# 12_Clock_2.net
KiCad netlist of a schematic drawn in Altium Designer
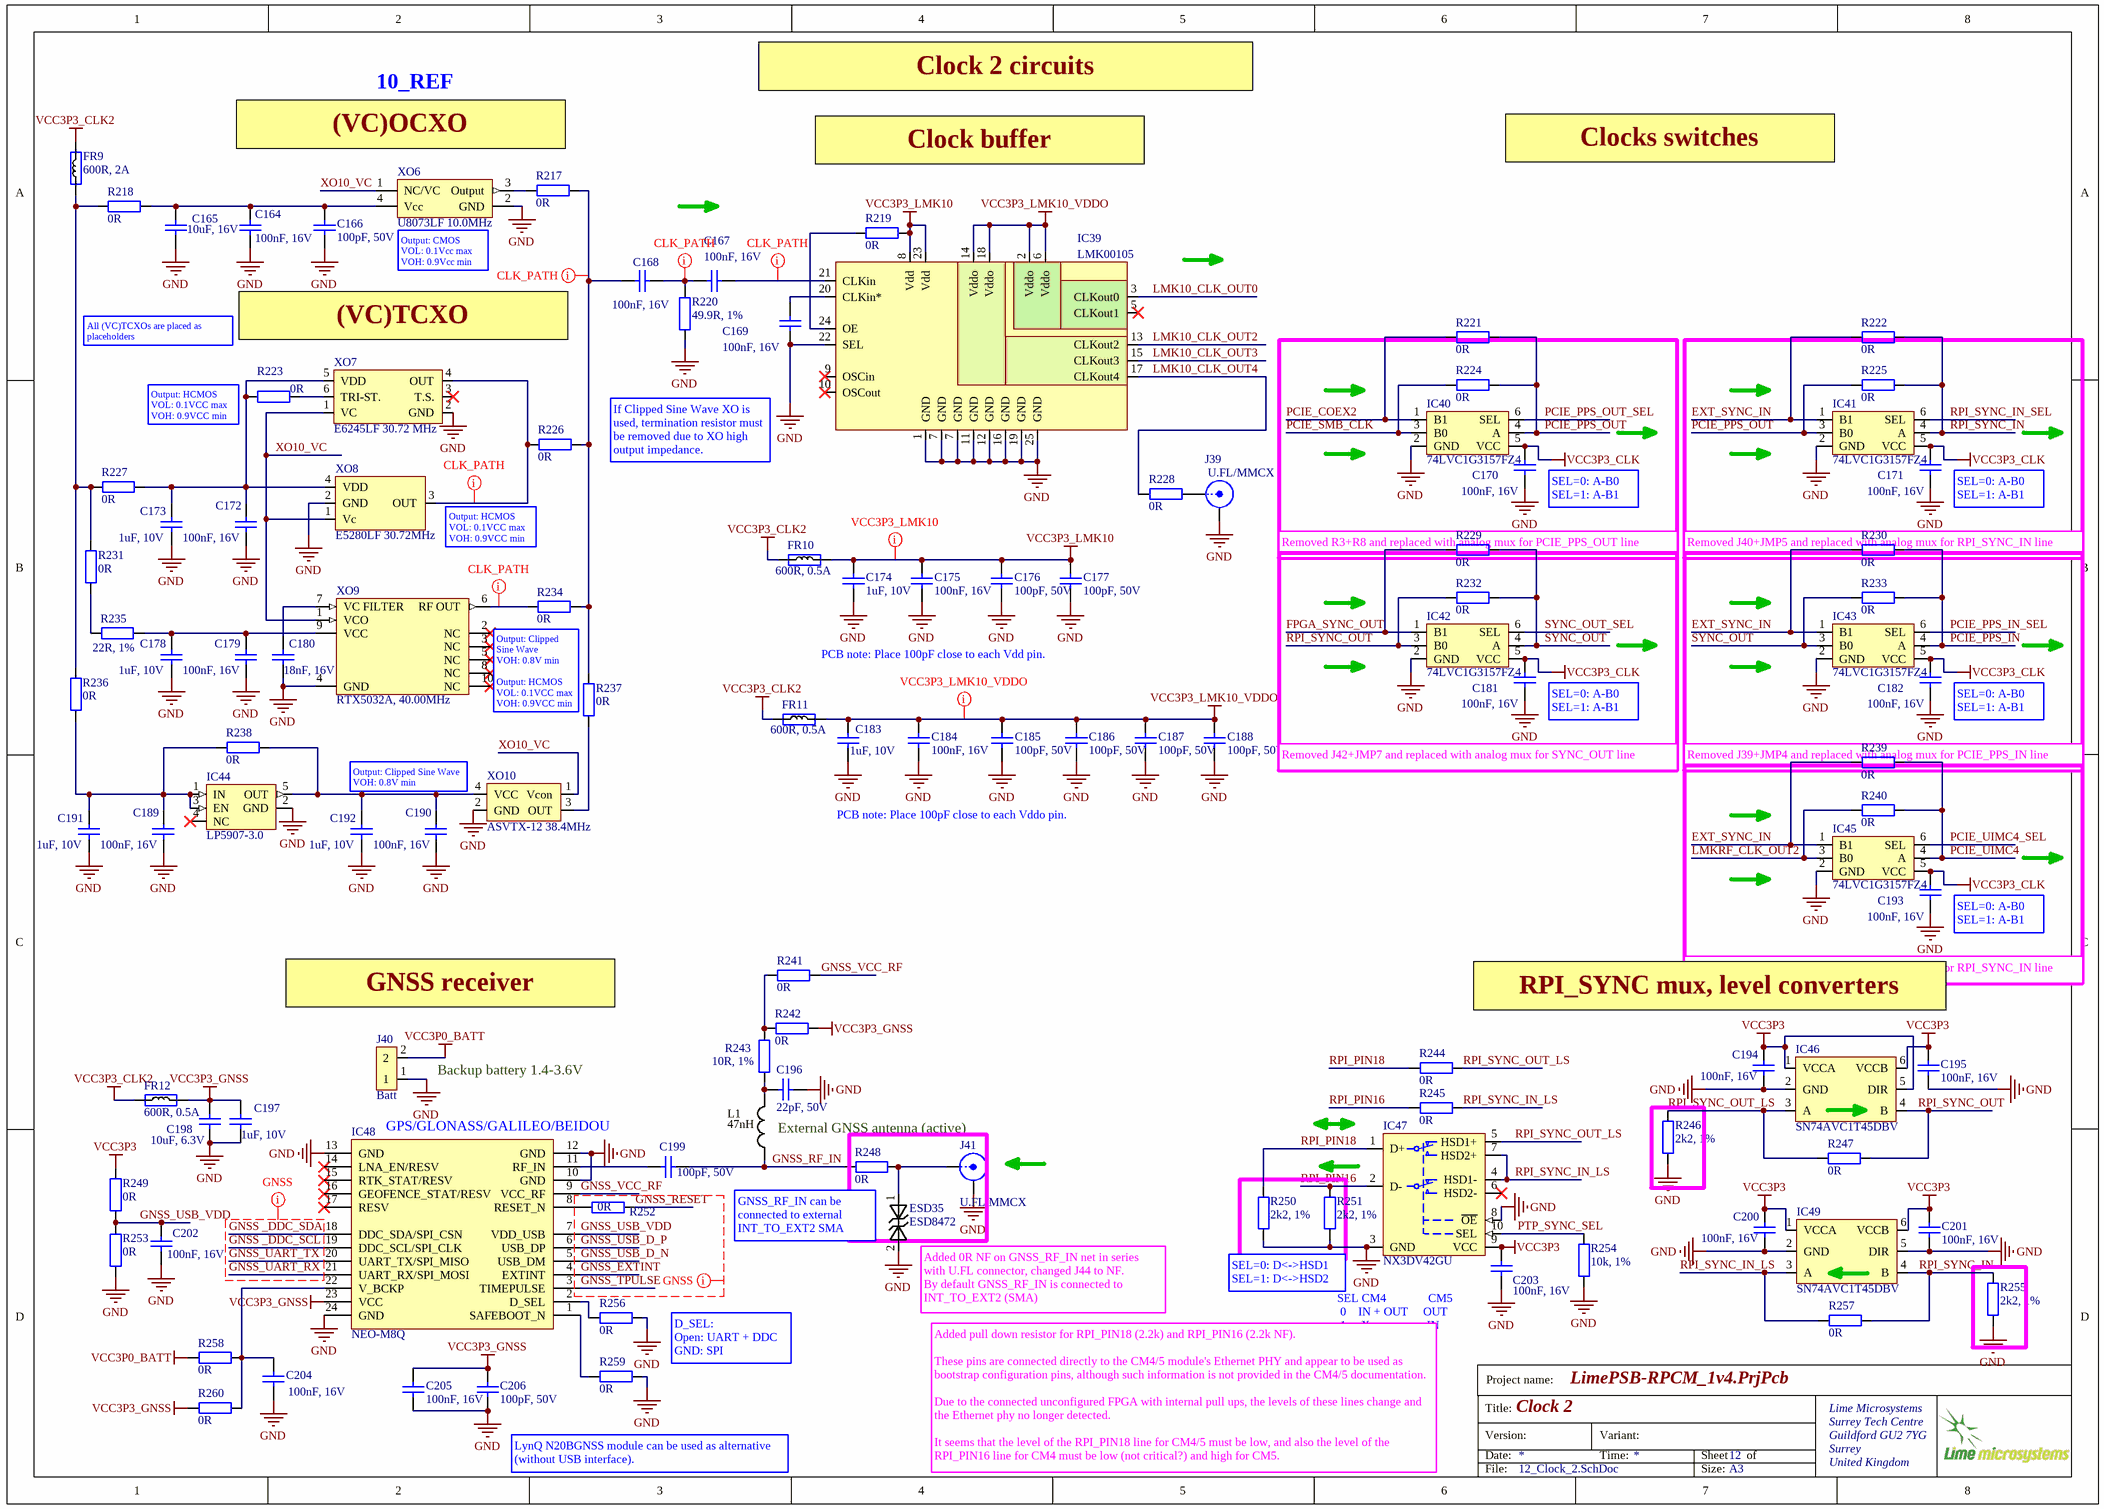
[diagram p0: 12_Clock_2.SchDoc]

(export (version "E")
  (design (tool "Eeschema 10.0.6"))
  (components
    (comp (ref "C164")
      (value "100nF, 16V")
      (footprint "CAP0402")
      (fields
        (field (name "MANUFACTURER") "Murata Electronics")
        (field (name "TOLERANCE") "10 %")
        (field (name "MANUFACTURER PART NUMBER") "GRM155R71C104KA88D")
      )
      (libsource (lib "LimeMicroAltiumLib_schLib") (part "Cap_0402"))
    )
    (comp (ref "C165")
      (value "10uF, 16V")
      (footprint "CAP0603")
      (fields (field (name "MANUFACTURER") "Yageo") (field (name "TOLERANCE") "±20%"))
      (libsource (lib "LimeMicroAltiumLib_schLib") (part "Cap_0603"))
    )
    (comp (ref "C166")
      (value "100pF, 50V")
      (footprint "CAP0402")
      (fields (field (name "TOLERANCE") "±5%") (field (name "MANUFACTURER") "Yageo"))
      (libsource (lib "LimeMicroAltiumLib_schLib") (part "Cap_0402"))
    )
    (comp (ref "C167")
      (value "100nF, 16V")
      (footprint "CAP0402")
      (fields
        (field (name "MANUFACTURER") "Murata Electronics")
        (field (name "TOLERANCE") "10 %")
        (field (name "MANUFACTURER PART NUMBER") "GRM155R71C104KA88D")
      )
      (libsource (lib "LimeMicroAltiumLib_schLib") (part "Cap_0402"))
    )
    (comp (ref "C168")
      (value "100nF, 16V")
      (footprint "CAP0402")
      (fields
        (field (name "MANUFACTURER") "Murata Electronics")
        (field (name "TOLERANCE") "10 %")
        (field (name "MANUFACTURER PART NUMBER") "GRM155R71C104KA88D")
      )
      (libsource (lib "LimeMicroAltiumLib_schLib") (part "Cap_0402"))
    )
    (comp (ref "C169")
      (value "100nF, 16V")
      (footprint "CAP0402")
      (fields
        (field (name "MANUFACTURER") "Murata Electronics")
        (field (name "TOLERANCE") "10 %")
        (field (name "MANUFACTURER PART NUMBER") "GRM155R71C104KA88D")
      )
      (libsource (lib "LimeMicroAltiumLib_schLib") (part "Cap_0402"))
    )
    (comp (ref "C170")
      (value "100nF, 16V")
      (footprint "CAP0402")
      (fields
        (field (name "MANUFACTURER") "Murata Electronics")
        (field (name "TOLERANCE") "10 %")
        (field (name "MANUFACTURER PART NUMBER") "GRM155R71C104KA88D")
      )
      (libsource (lib "LimeMicroAltiumLib_schLib") (part "Cap_0402"))
    )
    (comp (ref "C171")
      (value "100nF, 16V")
      (footprint "CAP0402")
      (fields
        (field (name "MANUFACTURER") "Murata Electronics")
        (field (name "TOLERANCE") "10 %")
        (field (name "MANUFACTURER PART NUMBER") "GRM155R71C104KA88D")
      )
      (libsource (lib "LimeMicroAltiumLib_schLib") (part "Cap_0402"))
    )
    (comp (ref "C172")
      (value "100nF, 16V")
      (footprint "CAP0402")
      (fields
        (field (name "MANUFACTURER") "Murata Electronics")
        (field (name "TOLERANCE") "10 %")
        (field (name "MANUFACTURER PART NUMBER") "GRM155R71C104KA88D")
      )
      (libsource (lib "LimeMicroAltiumLib_schLib") (part "Cap_0402"))
    )
    (comp (ref "C173")
      (value "1uF, 10V")
      (footprint "CAP0402")
      (description "CAP CER 1UF 10V X5R 0402")
      (fields (field (name "MANUFACTURER") "Yageo"))
      (libsource (lib "LimeMicroAltiumLib_schLib") (part "Cap_0402"))
    )
    (comp (ref "C174")
      (value "1uF, 10V")
      (footprint "CAP0402")
      (description "CAP CER 1UF 10V X5R 0402")
      (fields (field (name "MANUFACTURER") "Yageo") (field (name "TOLERANCE") "±20%"))
      (libsource (lib "LimeMicroAltiumLib_schLib") (part "Cap_0402"))
    )
    (comp (ref "C175")
      (value "100nF, 16V")
      (footprint "CAP0402")
      (fields
        (field (name "MANUFACTURER") "Murata Electronics")
        (field (name "TOLERANCE") "10 %")
        (field (name "MANUFACTURER PART NUMBER") "GRM155R71C104KA88D")
      )
      (libsource (lib "LimeMicroAltiumLib_schLib") (part "Cap_0402"))
    )
    (comp (ref "C176")
      (value "100pF, 50V")
      (footprint "CAP0402")
      (fields (field (name "MANUFACTURER") "Yageo") (field (name "TOLERANCE") "±5%"))
      (libsource (lib "LimeMicroAltiumLib_schLib") (part "Cap_0402"))
    )
    (comp (ref "C177")
      (value "100pF, 50V")
      (footprint "CAP0402")
      (fields (field (name "MANUFACTURER") "Yageo") (field (name "TOLERANCE") "±5%"))
      (libsource (lib "LimeMicroAltiumLib_schLib") (part "Cap_0402"))
    )
    (comp (ref "C178")
      (value "1uF, 10V")
      (footprint "CAP0402")
      (description "CAP CER 1UF 10V X5R 0402")
      (fields (field (name "MANUFACTURER") "Yageo"))
      (libsource (lib "LimeMicroAltiumLib_schLib") (part "Cap_0402"))
    )
    (comp (ref "C179")
      (value "100nF, 16V")
      (footprint "CAP0402")
      (fields
        (field (name "MANUFACTURER") "Murata Electronics")
        (field (name "TOLERANCE") "10 %")
        (field (name "MANUFACTURER PART NUMBER") "GRM155R71C104KA88D")
      )
      (libsource (lib "LimeMicroAltiumLib_schLib") (part "Cap_0402"))
    )
    (comp (ref "C180")
      (value "18nF, 16V")
      (footprint "CAP0402")
      (fields (field (name "MANUFACTURER") "Yageo") (field (name "TOLERANCE") "±10%"))
      (libsource (lib "LimeMicroAltiumLib_schLib") (part "Cap_0402"))
    )
    (comp (ref "C181")
      (value "100nF, 16V")
      (footprint "CAP0402")
      (fields
        (field (name "MANUFACTURER") "Murata Electronics")
        (field (name "TOLERANCE") "10 %")
        (field (name "MANUFACTURER PART NUMBER") "GRM155R71C104KA88D")
      )
      (libsource (lib "LimeMicroAltiumLib_schLib") (part "Cap_0402"))
    )
    (comp (ref "C182")
      (value "100nF, 16V")
      (footprint "CAP0402")
      (fields
        (field (name "MANUFACTURER") "Murata Electronics")
        (field (name "TOLERANCE") "10 %")
        (field (name "MANUFACTURER PART NUMBER") "GRM155R71C104KA88D")
      )
      (libsource (lib "LimeMicroAltiumLib_schLib") (part "Cap_0402"))
    )
    (comp (ref "C183")
      (value "1uF, 10V")
      (footprint "CAP0402")
      (description "CAP CER 1UF 10V X5R 0402")
      (fields (field (name "MANUFACTURER") "Yageo") (field (name "TOLERANCE") "±20%"))
      (libsource (lib "LimeMicroAltiumLib_schLib") (part "Cap_0402"))
    )
    (comp (ref "C184")
      (value "100nF, 16V")
      (footprint "CAP0402")
      (fields
        (field (name "MANUFACTURER") "Murata Electronics")
        (field (name "TOLERANCE") "10 %")
        (field (name "MANUFACTURER PART NUMBER") "GRM155R71C104KA88D")
      )
      (libsource (lib "LimeMicroAltiumLib_schLib") (part "Cap_0402"))
    )
    (comp (ref "C185")
      (value "100pF, 50V")
      (footprint "CAP0402")
      (fields (field (name "MANUFACTURER") "Yageo") (field (name "TOLERANCE") "±5%"))
      (libsource (lib "LimeMicroAltiumLib_schLib") (part "Cap_0402"))
    )
    (comp (ref "C186")
      (value "100pF, 50V")
      (footprint "CAP0402")
      (fields (field (name "MANUFACTURER") "Yageo") (field (name "TOLERANCE") "±5%"))
      (libsource (lib "LimeMicroAltiumLib_schLib") (part "Cap_0402"))
    )
    (comp (ref "C187")
      (value "100pF, 50V")
      (footprint "CAP0402")
      (fields (field (name "MANUFACTURER") "Yageo") (field (name "TOLERANCE") "±5%"))
      (libsource (lib "LimeMicroAltiumLib_schLib") (part "Cap_0402"))
    )
    (comp (ref "C188")
      (value "100pF, 50V")
      (footprint "CAP0402")
      (fields (field (name "MANUFACTURER") "Yageo") (field (name "TOLERANCE") "±5%"))
      (libsource (lib "LimeMicroAltiumLib_schLib") (part "Cap_0402"))
    )
    (comp (ref "C189")
      (value "100nF, 16V")
      (footprint "CAP0402")
      (fields
        (field (name "MANUFACTURER") "Murata Electronics")
        (field (name "TOLERANCE") "10 %")
        (field (name "MANUFACTURER PART NUMBER") "GRM155R71C104KA88D")
      )
      (libsource (lib "") (part "Cap_0402_1"))
    )
    (comp (ref "C190")
      (value "100nF, 16V")
      (footprint "CAP0402")
      (fields
        (field (name "MANUFACTURER") "Murata Electronics")
        (field (name "TOLERANCE") "10 %")
        (field (name "MANUFACTURER PART NUMBER") "GRM155R71C104KA88D")
      )
      (libsource (lib "") (part "Cap_0402_1"))
    )
    (comp (ref "C191")
      (value "1uF, 10V")
      (footprint "CAP0402")
      (fields (field (name "MANUFACTURER") "Yageo"))
      (libsource (lib "") (part "Cap_0402_1"))
    )
    (comp (ref "C192")
      (value "1uF, 10V")
      (footprint "CAP0402")
      (fields (field (name "MANUFACTURER") "Yageo"))
      (libsource (lib "") (part "Cap_0402_1"))
    )
    (comp (ref "C193")
      (value "100nF, 16V")
      (footprint "CAP0402")
      (fields
        (field (name "MANUFACTURER") "Murata Electronics")
        (field (name "TOLERANCE") "10 %")
        (field (name "MANUFACTURER PART NUMBER") "GRM155R71C104KA88D")
      )
      (libsource (lib "LimeMicroAltiumLib_schLib") (part "Cap_0402"))
    )
    (comp (ref "C194")
      (value "100nF, 16V")
      (footprint "CAP0402")
      (fields
        (field (name "MANUFACTURER") "Murata Electronics")
        (field (name "TOLERANCE") "10 %")
        (field (name "MANUFACTURER PART NUMBER") "GRM155R71C104KA88D")
      )
      (libsource (lib "LimeMicroAltiumLib_schLib") (part "Cap_0402"))
    )
    (comp (ref "C195")
      (value "100nF, 16V")
      (footprint "CAP0402")
      (fields
        (field (name "MANUFACTURER") "Murata Electronics")
        (field (name "TOLERANCE") "10 %")
        (field (name "MANUFACTURER PART NUMBER") "GRM155R71C104KA88D")
      )
      (libsource (lib "LimeMicroAltiumLib_schLib") (part "Cap_0402"))
    )
    (comp (ref "C196")
      (value "22pF, 50V")
      (footprint "CAP0402")
      (fields (field (name "TOLERANCE") "±5%") (field (name "MANUFACTURER") "Yageo"))
      (libsource (lib "LimeMicroAltiumLib_schLib") (part "Cap_0402"))
    )
    (comp (ref "C197")
      (value "1uF, 10V")
      (footprint "CAP0402")
      (description "CAP CER 1UF 10V X5R 0402")
      (fields (field (name "MANUFACTURER") "Yageo") (field (name "TOLERANCE") "±20%"))
      (libsource (lib "LimeMicroAltiumLib_schLib") (part "Cap_0402"))
    )
    (comp (ref "C198")
      (value "10uF, 6.3V")
      (footprint "CAP0603")
      (fields (field (name "TOLERANCE") "±20%") (field (name "MANUFACTURER") "Yageo"))
      (libsource (lib "LimeFPGAboard_schLib") (part "Cap_0603"))
    )
    (comp (ref "C199")
      (value "100pF, 50V")
      (footprint "CAP0402")
      (fields (field (name "TOLERANCE") "±5%") (field (name "MANUFACTURER") "Yageo"))
      (libsource (lib "LimeMicroAltiumLib_schLib") (part "Cap_0402"))
    )
    (comp (ref "C200")
      (value "100nF, 16V")
      (footprint "CAP0402")
      (fields
        (field (name "MANUFACTURER") "Murata Electronics")
        (field (name "TOLERANCE") "10 %")
        (field (name "MANUFACTURER PART NUMBER") "GRM155R71C104KA88D")
      )
      (libsource (lib "LimeMicroAltiumLib_schLib") (part "Cap_0402"))
    )
    (comp (ref "C201")
      (value "100nF, 16V")
      (footprint "CAP0402")
      (fields
        (field (name "MANUFACTURER") "Murata Electronics")
        (field (name "TOLERANCE") "10 %")
        (field (name "MANUFACTURER PART NUMBER") "GRM155R71C104KA88D")
      )
      (libsource (lib "LimeMicroAltiumLib_schLib") (part "Cap_0402"))
    )
    (comp (ref "C202")
      (value "100nF, 16V")
      (footprint "CAP0402")
      (fields
        (field (name "TOLERANCE") "10 %")
        (field (name "MANUFACTURER") "Murata Electronics")
        (field (name "MANUFACTURER PART NUMBER") "GRM155R71C104KA88D")
      )
      (libsource (lib "LimeFPGAboard_schLib") (part "Cap_0603"))
    )
    (comp (ref "C203")
      (value "100nF, 16V")
      (footprint "CAP0402")
      (fields
        (field (name "MANUFACTURER") "Murata Electronics")
        (field (name "TOLERANCE") "10 %")
        (field (name "MANUFACTURER PART NUMBER") "GRM155R71C104KA88D")
      )
      (libsource (lib "LimeMicroAltiumLib_schLib") (part "Cap_0402"))
    )
    (comp (ref "C204")
      (value "100nF, 16V")
      (footprint "CAP0402")
      (fields
        (field (name "TOLERANCE") "10 %")
        (field (name "MANUFACTURER") "Murata Electronics")
        (field (name "MANUFACTURER PART NUMBER") "GRM155R71C104KA88D")
      )
      (libsource (lib "LimeFPGAboard_schLib") (part "Cap_0603"))
    )
    (comp (ref "C205")
      (value "100nF, 16V")
      (footprint "CAP0402")
      (fields
        (field (name "MANUFACTURER") "Murata Electronics")
        (field (name "TOLERANCE") "10 %")
        (field (name "MANUFACTURER PART NUMBER") "GRM155R71C104KA88D")
      )
      (libsource (lib "LimeMicroAltiumLib_schLib") (part "Cap_0402"))
    )
    (comp (ref "C206")
      (value "100pF, 50V")
      (footprint "CAP0402")
      (fields (field (name "TOLERANCE") "±5%") (field (name "MANUFACTURER") "Yageo"))
      (libsource (lib "LimeMicroAltiumLib_schLib") (part "Cap_0402"))
    )
    (comp (ref "ESD35")
      (value "ESD8472")
      (footprint "ESD8472_X3DFN2")
      (fields
        (field (name "MANUFACTURER") "ON Semiconductor")
        (field (name "MANUFACTURER PART NUMBER") "ESD8472MUT5G")
      )
      (libsource (lib "LimeMicroAltiumLib_schLib") (part "ESD8472"))
    )
    (comp (ref "FR9")
      (value "600R, 2A")
      (footprint "RES0805")
      (fields (field (name "MANUFACTURER") "TDK Corporation"))
      (libsource (lib "LimeFPGAboard_schLib") (part "Ferrite"))
    )
    (comp (ref "FR10")
      (value "600R, 0.5A")
      (footprint "RES0402")
      (fields (field (name "MANUFACTURER") "Murata") (field (name "TOLERANCE") "25%"))
      (libsource (lib "LimeMicroAltiumLib_schLib") (part "Ferrite"))
    )
    (comp (ref "FR11")
      (value "600R, 0.5A")
      (footprint "RES0402")
      (fields (field (name "MANUFACTURER") "Murata") (field (name "TOLERANCE") "25%"))
      (libsource (lib "LimeMicroAltiumLib_schLib") (part "Ferrite"))
    )
    (comp (ref "FR12")
      (value "600R, 0.5A")
      (footprint "RES0402")
      (fields (field (name "MANUFACTURER") "Murata") (field (name "TOLERANCE") "25%"))
      (libsource (lib "LimeMicroAltiumLib_schLib") (part "Ferrite"))
    )
    (comp (ref "IC39")
      (value "LMK00105")
      (footprint "LMK00105SQ")
      (fields (field (name "MANUFACTURER") "Texas Instruments"))
      (libsource (lib "LimeMicroAltiumLib_schLib") (part "LMK00105"))
    )
    (comp (ref "IC40")
      (value "74LVC1G3157FZ4")
      (footprint "74LVC1G3157FZ4_SPDT_SW_DFN1410-6")
      (fields (field (name "MANUFACTURER") "Diodes"))
      (libsource (lib "LimeMicroAltiumLib_schLib_r04") (part "74LVC1G3157FZ4_SPDT_SW"))
    )
    (comp (ref "IC41")
      (value "74LVC1G3157FZ4")
      (footprint "74LVC1G3157FZ4_SPDT_SW_DFN1410-6")
      (fields (field (name "MANUFACTURER") "Diodes"))
      (libsource (lib "LimeMicroAltiumLib_schLib_r04") (part "74LVC1G3157FZ4_SPDT_SW"))
    )
    (comp (ref "IC42")
      (value "74LVC1G3157FZ4")
      (footprint "74LVC1G3157FZ4_SPDT_SW_DFN1410-6")
      (fields (field (name "MANUFACTURER") "Diodes"))
      (libsource (lib "LimeMicroAltiumLib_schLib_r04") (part "74LVC1G3157FZ4_SPDT_SW"))
    )
    (comp (ref "IC43")
      (value "74LVC1G3157FZ4")
      (footprint "74LVC1G3157FZ4_SPDT_SW_DFN1410-6")
      (fields (field (name "MANUFACTURER") "Diodes"))
      (libsource (lib "LimeMicroAltiumLib_schLib_r04") (part "74LVC1G3157FZ4_SPDT_SW"))
    )
    (comp (ref "IC44")
      (value "LP5907-3.0")
      (footprint "SOT23-5")
      (fields (field (name "MANUFACTURER") "Texas Instruments"))
      (libsource (lib "LimeMicroAltiumLib_schLib_r01") (part "LP5907"))
    )
    (comp (ref "IC45")
      (value "74LVC1G3157FZ4")
      (footprint "74LVC1G3157FZ4_SPDT_SW_DFN1410-6")
      (fields (field (name "MANUFACTURER") "Diodes"))
      (libsource (lib "LimeMicroAltiumLib_schLib_r04") (part "74LVC1G3157FZ4_SPDT_SW"))
    )
    (comp (ref "IC46")
      (value "SN74AVC1T45DBV")
      (footprint "SOT23-6")
      (fields (field (name "MANUFACTURER") "Texas Instruments"))
      (libsource (lib "LimeMicroAltiumLib_schLib_r04") (part "SN74AVC1T45DBV"))
    )
    (comp (ref "IC47")
      (value "NX3DV42GU")
      (footprint "FSUSB42UMX")
      (fields (field (name "MANUFACTURER") "NXP Semiconductors"))
      (libsource (lib "LimeMicroAltiumLib_schLib_r01") (part "FSUSB42UMX"))
    )
    (comp (ref "IC48")
      (value "NEO-M8Q")
      (footprint "NEO-7M/8M")
      (description "GNSS engine for GPS/QZSS, GLONASS")
      (fields (field (name "MANUFACTURER") "U-blox"))
      (libsource (lib "LimeMicroAltiumLib_schLib") (part "NEO-M8P_M8M"))
    )
    (comp (ref "IC49")
      (value "SN74AVC1T45DBV")
      (footprint "SOT23-6")
      (fields (field (name "MANUFACTURER") "Texas Instruments"))
      (libsource (lib "LimeMicroAltiumLib_schLib_r04") (part "SN74AVC1T45DBV"))
    )
    (comp (ref "J39")
      (value "U.FL/MMCX")
      (footprint "MMCX_UFL_conn_u")
      (description "CONN UMC RCPT STR 50 OHM SMD")
      (fields (field (name "MANUFACTURER") "Molex, LLC"))
      (libsource (lib "LimeMicroAltiumLib_schLib") (part "RF_IF_connector"))
    )
    (comp (ref "J40")
      (value "Batt")
      (footprint "HDR_1x2")
      (fields (field (name "MANUFACTURER") "3M"))
      (libsource (lib "LimeFPGAboard_schLib") (part "Jumper"))
    )
    (comp (ref "J41")
      (value "U.FL/MMCX")
      (footprint "MMCX_UFL_conn_u")
      (description "CONN UMC RCPT STR 50 OHM SMD")
      (fields (field (name "MANUFACTURER") "Molex, LLC"))
      (libsource (lib "LimeMicroAltiumLib_schLib") (part "RF_IF_connector"))
    )
    (comp (ref "L1")
      (value "47nH")
      (footprint "RES0402")
      (fields
        (field (name "MANUFACTURER") "COILCRAFT")
        (field (name "MANUFACTURER PART NUMBER") "0402HP-47NXJLU")
      )
      (libsource (lib "LimeMicroAltiumLib_schLib") (part "Inductor_0603"))
    )
    (comp (ref "R217")
      (value "0R")
      (footprint "RES0402_v2")
      (fields (field (name "MANUFACTURER") "Yageo") (field (name "TOLERANCE") "Jumper"))
      (libsource (lib "LimeMicroAltiumLib_schLib") (part "Res_0402"))
    )
    (comp (ref "R218")
      (value "0R")
      (footprint "RES0402")
      (fields (field (name "MANUFACTURER") "Yageo") (field (name "TOLERANCE") "Jumper"))
      (libsource (lib "LimeMicroAltiumLib_schLib") (part "Res_0402"))
    )
    (comp (ref "R219")
      (value "0R")
      (footprint "RES0402")
      (fields (field (name "MANUFACTURER") "Yageo") (field (name "TOLERANCE") "Jumper"))
      (libsource (lib "LimeMicroAltiumLib_schLib") (part "Res_0402"))
    )
    (comp (ref "R220")
      (value "49.9R, 1%")
      (footprint "RES0402")
      (fields
        (field (name "TOLERANCE") "±1%")
        (field (name "MANUFACTURER") "Samsung Electro-Mechanics America, Inc.")
      )
      (libsource (lib "LimeMicroAltiumLib_schLib") (part "Res_0402"))
    )
    (comp (ref "R221")
      (value "0R")
      (footprint "RES0402_v2")
      (fields (field (name "MANUFACTURER") "Yageo") (field (name "TOLERANCE") "Jumper"))
      (libsource (lib "LimeMicroAltiumLib_schLib") (part "Res_0402"))
    )
    (comp (ref "R222")
      (value "0R")
      (footprint "RES0402_v2")
      (fields (field (name "MANUFACTURER") "Yageo") (field (name "TOLERANCE") "Jumper"))
      (libsource (lib "LimeMicroAltiumLib_schLib") (part "Res_0402"))
    )
    (comp (ref "R223")
      (value "0R")
      (footprint "RES0402")
      (fields (field (name "MANUFACTURER") "Yageo") (field (name "TOLERANCE") "Jumper"))
      (libsource (lib "LimeMicroAltiumLib_schLib") (part "Res_0402"))
    )
    (comp (ref "R224")
      (value "0R")
      (footprint "RES0402_v2")
      (fields (field (name "MANUFACTURER") "Yageo") (field (name "TOLERANCE") "Jumper"))
      (libsource (lib "LimeMicroAltiumLib_schLib") (part "Res_0402"))
    )
    (comp (ref "R225")
      (value "0R")
      (footprint "RES0402_v2")
      (fields (field (name "MANUFACTURER") "Yageo") (field (name "TOLERANCE") "Jumper"))
      (libsource (lib "LimeMicroAltiumLib_schLib") (part "Res_0402"))
    )
    (comp (ref "R226")
      (value "0R")
      (footprint "RES0402_v2")
      (fields (field (name "MANUFACTURER") "Yageo") (field (name "TOLERANCE") "Jumper"))
      (libsource (lib "LimeMicroAltiumLib_schLib") (part "Res_0402"))
    )
    (comp (ref "R227")
      (value "0R")
      (footprint "RES0402")
      (fields (field (name "MANUFACTURER") "Yageo") (field (name "TOLERANCE") "Jumper"))
      (libsource (lib "LimeMicroAltiumLib_schLib") (part "Res_0402"))
    )
    (comp (ref "R228")
      (value "0R")
      (footprint "RES0402")
      (fields (field (name "MANUFACTURER") "Yageo") (field (name "TOLERANCE") "Jumper"))
      (libsource (lib "") (part "Res_0402_1"))
    )
    (comp (ref "R229")
      (value "0R")
      (footprint "RES0402_v2")
      (fields (field (name "MANUFACTURER") "Yageo") (field (name "TOLERANCE") "Jumper"))
      (libsource (lib "LimeMicroAltiumLib_schLib") (part "Res_0402"))
    )
    (comp (ref "R230")
      (value "0R")
      (footprint "RES0402_v2")
      (fields (field (name "MANUFACTURER") "Yageo") (field (name "TOLERANCE") "Jumper"))
      (libsource (lib "LimeMicroAltiumLib_schLib") (part "Res_0402"))
    )
    (comp (ref "R231")
      (value "0R")
      (footprint "RES0402")
      (fields (field (name "MANUFACTURER") "Yageo") (field (name "TOLERANCE") "Jumper"))
      (libsource (lib "LimeMicroAltiumLib_schLib") (part "Res_0402"))
    )
    (comp (ref "R232")
      (value "0R")
      (footprint "RES0402_v2")
      (fields (field (name "MANUFACTURER") "Yageo") (field (name "TOLERANCE") "Jumper"))
      (libsource (lib "LimeMicroAltiumLib_schLib") (part "Res_0402"))
    )
    (comp (ref "R233")
      (value "0R")
      (footprint "RES0402_v2")
      (fields (field (name "MANUFACTURER") "Yageo") (field (name "TOLERANCE") "Jumper"))
      (libsource (lib "LimeMicroAltiumLib_schLib") (part "Res_0402"))
    )
    (comp (ref "R234")
      (value "0R")
      (footprint "RES0402_v2")
      (fields (field (name "MANUFACTURER") "Yageo") (field (name "TOLERANCE") "Jumper"))
      (libsource (lib "LimeMicroAltiumLib_schLib") (part "Res_0402"))
    )
    (comp (ref "R235")
      (value "22R, 1%")
      (footprint "RES0402")
      (fields (field (name "TOLERANCE") "±1%") (field (name "MANUFACTURER") "Yageo"))
      (libsource (lib "LimeFPGAboard_schLib") (part "Res_0402"))
    )
    (comp (ref "R236")
      (value "0R")
      (footprint "RES0402")
      (fields (field (name "MANUFACTURER") "Yageo") (field (name "TOLERANCE") "Jumper"))
      (libsource (lib "") (part "Res_0402_1"))
    )
    (comp (ref "R237")
      (value "0R")
      (footprint "RES0402_v2")
      (fields (field (name "MANUFACTURER") "Yageo") (field (name "TOLERANCE") "Jumper"))
      (libsource (lib "") (part "Res_0402_1"))
    )
    (comp (ref "R238")
      (value "0R")
      (footprint "RES0402")
      (fields (field (name "MANUFACTURER") "Yageo") (field (name "TOLERANCE") "Jumper"))
      (libsource (lib "") (part "Res_0402_1"))
    )
    (comp (ref "R239")
      (value "0R")
      (footprint "RES0402_v2")
      (fields (field (name "MANUFACTURER") "Yageo") (field (name "TOLERANCE") "Jumper"))
      (libsource (lib "LimeMicroAltiumLib_schLib") (part "Res_0402"))
    )
    (comp (ref "R240")
      (value "0R")
      (footprint "RES0402_v2")
      (fields (field (name "MANUFACTURER") "Yageo") (field (name "TOLERANCE") "Jumper"))
      (libsource (lib "LimeMicroAltiumLib_schLib") (part "Res_0402"))
    )
    (comp (ref "R241")
      (value "0R")
      (footprint "RES0402")
      (fields (field (name "MANUFACTURER") "Yageo") (field (name "TOLERANCE") "Jumper"))
      (libsource (lib "LimeMicroAltiumLib_schLib") (part "Res_0402"))
    )
    (comp (ref "R242")
      (value "0R")
      (footprint "RES0402")
      (fields (field (name "MANUFACTURER") "Yageo") (field (name "TOLERANCE") "Jumper"))
      (libsource (lib "LimeMicroAltiumLib_schLib") (part "Res_0402"))
    )
    (comp (ref "R243")
      (value "10R, 1%")
      (footprint "RES0402")
      (fields (field (name "MANUFACTURER") "Stackpole Electronics") (field (name "TOLERANCE") "1%"))
      (libsource (lib "LimeMicroAltiumLib_schLib") (part "Res_0402"))
    )
    (comp (ref "R244")
      (value "0R")
      (footprint "RES0402")
      (fields (field (name "MANUFACTURER") "Yageo") (field (name "TOLERANCE") "Jumper"))
      (libsource (lib "") (part "Res_0402_1"))
    )
    (comp (ref "R245")
      (value "0R")
      (footprint "RES0402")
      (fields (field (name "MANUFACTURER") "Yageo") (field (name "TOLERANCE") "Jumper"))
      (libsource (lib "") (part "Res_0402_1"))
    )
    (comp (ref "R246")
      (value "2k2, 1%")
      (footprint "RES0402")
      (fields (field (name "MANUFACTURER") "Stackpole Electronics Inc") (field (name "TOLERANCE") "±1%"))
      (libsource (lib "LimeMicroAltiumLib_schLib") (part "Res_0402"))
    )
    (comp (ref "R247")
      (value "0R")
      (footprint "RES0402")
      (fields (field (name "MANUFACTURER") "Yageo") (field (name "TOLERANCE") "Jumper"))
      (libsource (lib "LimeFPGAboard_schLib") (part "Res_0402"))
    )
    (comp (ref "R248")
      (value "0R")
      (footprint "RES0402_v2")
      (fields (field (name "MANUFACTURER") "Yageo") (field (name "TOLERANCE") "Jumper"))
      (libsource (lib "") (part "Res_0402_1"))
    )
    (comp (ref "R249")
      (value "0R")
      (footprint "RES0402")
      (fields (field (name "MANUFACTURER") "Yageo") (field (name "TOLERANCE") "Jumper"))
      (libsource (lib "LimeMicroAltiumLib_schLib") (part "Res_0402"))
    )
    (comp (ref "R250")
      (value "2k2, 1%")
      (footprint "RES0402")
      (fields (field (name "MANUFACTURER") "Stackpole Electronics Inc") (field (name "TOLERANCE") "±1%"))
      (libsource (lib "LimeMicroAltiumLib_schLib") (part "Res_0402"))
    )
    (comp (ref "R251")
      (value "2k2, 1%")
      (footprint "RES0402")
      (fields (field (name "MANUFACTURER") "Stackpole Electronics Inc") (field (name "TOLERANCE") "±1%"))
      (libsource (lib "LimeMicroAltiumLib_schLib") (part "Res_0402"))
    )
    (comp (ref "R252")
      (value "0R")
      (footprint "RES0402")
      (fields (field (name "MANUFACTURER") "Yageo") (field (name "TOLERANCE") "Jumper"))
      (libsource (lib "LimeMicroAltiumLib_schLib") (part "Res_0402"))
    )
    (comp (ref "R253")
      (value "0R")
      (footprint "RES0402")
      (fields (field (name "MANUFACTURER") "Yageo") (field (name "TOLERANCE") "Jumper"))
      (libsource (lib "LimeMicroAltiumLib_schLib") (part "Res_0402"))
    )
    (comp (ref "R254")
      (value "10k, 1%")
      (footprint "RES0402")
      (fields (field (name "MANUFACTURER") "Yageo") (field (name "TOLERANCE") "±1%"))
      (libsource (lib "LimeMicroAltiumLib_schLib") (part "Res_0402"))
    )
    (comp (ref "R255")
      (value "2k2, 1%")
      (footprint "RES0402")
      (fields (field (name "MANUFACTURER") "Stackpole Electronics Inc") (field (name "TOLERANCE") "±1%"))
      (libsource (lib "LimeMicroAltiumLib_schLib") (part "Res_0402"))
    )
    (comp (ref "R256")
      (value "0R")
      (footprint "RES0402")
      (fields (field (name "MANUFACTURER") "Yageo") (field (name "TOLERANCE") "Jumper"))
      (libsource (lib "LimeMicroAltiumLib_schLib") (part "Res_0402"))
    )
    (comp (ref "R257")
      (value "0R")
      (footprint "RES0402")
      (fields (field (name "MANUFACTURER") "Yageo") (field (name "TOLERANCE") "Jumper"))
      (libsource (lib "LimeFPGAboard_schLib") (part "Res_0402"))
    )
    (comp (ref "R258")
      (value "0R")
      (footprint "RES0402")
      (fields (field (name "MANUFACTURER") "Yageo") (field (name "TOLERANCE") "Jumper"))
      (libsource (lib "LimeMicroAltiumLib_schLib") (part "Res_0402"))
    )
    (comp (ref "R259")
      (value "0R")
      (footprint "RES0402")
      (fields (field (name "MANUFACTURER") "Yageo") (field (name "TOLERANCE") "Jumper"))
      (libsource (lib "LimeMicroAltiumLib_schLib") (part "Res_0402"))
    )
    (comp (ref "R260")
      (value "0R")
      (footprint "RES0402")
      (fields (field (name "MANUFACTURER") "Yageo") (field (name "TOLERANCE") "Jumper"))
      (libsource (lib "LimeMicroAltiumLib_schLib") (part "Res_0402"))
    )
    (comp (ref "XO6")
      (value "U8073LF 10.0MHz")
      (footprint "AOCJYR-10.000MHz")
      (fields (field (name "MANUFACTURER") "Rakon"))
      (libsource (lib "LimeMicroAltiumLib_schLib") (part "AOCJYR-10.000MHz"))
    )
    (comp (ref "XO7")
      (value "E6245LF 30.72 MHz")
      (footprint "RAKON_RPT7050A")
      (fields (field (name "MANUFACTURER") "Rakon"))
      (libsource (lib "LimeMicroAltiumLib_schLib") (part "RPT7050A"))
    )
    (comp (ref "XO8")
      (value "E5280LF 30.72MHz")
      (footprint "RAKON_TXCO")
      (fields (field (name "MANUFACTURER") "Rakon"))
      (libsource (lib "LimeMicroAltiumLib_schLib") (part "TXCO"))
    )
    (comp (ref "XO9")
      (value "RTX5032A, 40.00MHz")
      (footprint "RAKON_RTX5032A")
      (fields (field (name "MANUFACTURER") "Rakon"))
      (libsource (lib "LimeMicroAltiumLib_schLib") (part "Rakon_RTX5032A"))
    )
    (comp (ref "XO10")
      (value "ASVTX-12 38.4MHz")
      (footprint "CRYSTAL_4-LCC_2P5x2P0")
      (description "Oscillator Crystal")
      (fields (field (name "MANUFACTURER") "Abracon"))
      (libsource (lib "LimeMicroAltiumLib_schLib_r01") (part "ASVTX-12-A-38.400MHZ-H10-T_CRYSTAL"))
    )
  )
  (nets
    (net (code "1") (name "/EXT_SYNC_IN") (class "Default")
      (node (ref "IC41") (pin "1") (pinfunction "B1_1") (pintype "passive"))
      (node (ref "IC43") (pin "1") (pinfunction "B1_1") (pintype "passive"))
      (node (ref "IC45") (pin "1") (pinfunction "B1_1") (pintype "passive"))
      (node (ref "R222") (pin "2") (pinfunction "2_2") (pintype "passive"))
      (node (ref "R230") (pin "2") (pinfunction "2_2") (pintype "passive"))
      (node (ref "R239") (pin "2") (pinfunction "2_2") (pintype "passive"))
    )
    (net (code "2") (name "/FPGA_SYNC_OUT") (class "Default")
      (node (ref "IC42") (pin "1") (pinfunction "B1_1") (pintype "passive"))
      (node (ref "R229") (pin "2") (pinfunction "2_2") (pintype "passive"))
    )
    (net (code "3") (name "/GNSS _DDC_SCL") (class "Default")
      (node (ref "IC48") (pin "19") (pinfunction "DDC_SCL/SPI_CLK_19") (pintype "passive"))
    )
    (net (code "4") (name "/GNSS _DDC_SDA") (class "Default")
      (node (ref "IC48") (pin "18") (pinfunction "DDC_SDA/SPI_CSN_18") (pintype "passive"))
    )
    (net (code "5") (name "/GNSS_EXTINT") (class "Default")
      (node (ref "IC48") (pin "4") (pinfunction "EXTINT_4") (pintype "passive"))
    )
    (net (code "6") (name "/GNSS_RESET") (class "Default")
      (node (ref "R252") (pin "1") (pinfunction "1_1") (pintype "passive"))
    )
    (net (code "7") (name "/GNSS_RF_IN") (class "Default")
      (node (ref "C199") (pin "1") (pinfunction "1_1") (pintype "passive"))
      (node (ref "L1") (pin "1") (pinfunction "1_1") (pintype "passive"))
      (node (ref "R248") (pin "2") (pinfunction "2_2") (pintype "passive"))
    )
    (net (code "8") (name "/GNSS_TPULSE") (class "Default")
      (node (ref "IC48") (pin "3") (pinfunction "TIMEPULSE_3") (pintype "passive"))
    )
    (net (code "9") (name "/GNSS_UART_RX") (class "Default")
      (node (ref "IC48") (pin "21") (pinfunction "UART_RX/SPI_MOSI_21") (pintype "passive"))
    )
    (net (code "10") (name "/GNSS_UART_TX") (class "Default")
      (node (ref "IC48") (pin "20") (pinfunction "UART_TX/SPI_MISO_20") (pintype "passive"))
    )
    (net (code "11") (name "/GNSS_USB_D_N") (class "Default")
      (node (ref "IC48") (pin "5") (pinfunction "USB_DM_5") (pintype "passive"))
    )
    (net (code "12") (name "/GNSS_USB_D_P") (class "Default")
      (node (ref "IC48") (pin "6") (pinfunction "USB_DP_6") (pintype "passive"))
    )
    (net (code "13") (name "/GNSS_USB_VDD") (class "Default")
      (node (ref "C202") (pin "1") (pinfunction "1_1") (pintype "passive"))
      (node (ref "IC48") (pin "7") (pinfunction "VDD_USB_7") (pintype "passive"))
      (node (ref "R249") (pin "2") (pinfunction "2_2") (pintype "passive"))
      (node (ref "R253") (pin "2") (pinfunction "2_2") (pintype "passive"))
    )
    (net (code "14") (name "/GNSS_VCC_RF") (class "Default")
      (node (ref "IC48") (pin "9") (pinfunction "VCC_RF_9") (pintype "passive"))
      (node (ref "R241") (pin "2") (pinfunction "2_2") (pintype "passive"))
    )
    (net (code "15") (name "/LMK10_CLK_OUT0") (class "Default")
      (node (ref "IC39") (pin "3") (pinfunction "CLKout0_3") (pintype "passive"))
    )
    (net (code "16") (name "/LMK10_CLK_OUT2") (class "Default")
      (node (ref "IC39") (pin "13") (pinfunction "CLKout2_13") (pintype "passive"))
    )
    (net (code "17") (name "/LMK10_CLK_OUT3") (class "Default")
      (node (ref "IC39") (pin "15") (pinfunction "CLKout3_15") (pintype "passive"))
    )
    (net (code "18") (name "/LMK10_CLK_OUT4") (class "Default")
      (node (ref "IC39") (pin "17") (pinfunction "CLKout4_17") (pintype "passive"))
      (node (ref "R228") (pin "2") (pinfunction "2_2") (pintype "passive"))
    )
    (net (code "19") (name "/LMKRF_CLK_OUT2") (class "Default")
      (node (ref "IC45") (pin "3") (pinfunction "B0_3") (pintype "passive"))
      (node (ref "R240") (pin "2") (pinfunction "2_2") (pintype "passive"))
    )
    (net (code "20") (name "/PCIE_COEX2") (class "Default")
      (node (ref "IC40") (pin "1") (pinfunction "B1_1") (pintype "passive"))
      (node (ref "R221") (pin "2") (pinfunction "2_2") (pintype "passive"))
    )
    (net (code "21") (name "/PCIE_PPS_IN") (class "Default")
      (node (ref "IC43") (pin "4") (pinfunction "A_4") (pintype "passive"))
      (node (ref "R230") (pin "1") (pinfunction "1_1") (pintype "passive"))
      (node (ref "R233") (pin "1") (pinfunction "1_1") (pintype "passive"))
    )
    (net (code "22") (name "/PCIE_PPS_IN_SEL") (class "Default")
      (node (ref "IC43") (pin "6") (pinfunction "SEL_6") (pintype "passive"))
    )
    (net (code "23") (name "/PCIE_PPS_OUT") (class "Default")
      (node (ref "IC40") (pin "4") (pinfunction "A_4") (pintype "passive"))
      (node (ref "IC41") (pin "3") (pinfunction "B0_3") (pintype "passive"))
      (node (ref "R221") (pin "1") (pinfunction "1_1") (pintype "passive"))
      (node (ref "R224") (pin "1") (pinfunction "1_1") (pintype "passive"))
      (node (ref "R225") (pin "2") (pinfunction "2_2") (pintype "passive"))
    )
    (net (code "24") (name "/PCIE_PPS_OUT_SEL") (class "Default")
      (node (ref "IC40") (pin "6") (pinfunction "SEL_6") (pintype "passive"))
    )
    (net (code "25") (name "/PCIE_SMB_CLK") (class "Default")
      (node (ref "IC40") (pin "3") (pinfunction "B0_3") (pintype "passive"))
      (node (ref "R224") (pin "2") (pinfunction "2_2") (pintype "passive"))
    )
    (net (code "26") (name "/PCIE_UIMC4") (class "Default")
      (node (ref "IC45") (pin "4") (pinfunction "A_4") (pintype "passive"))
      (node (ref "R239") (pin "1") (pinfunction "1_1") (pintype "passive"))
      (node (ref "R240") (pin "1") (pinfunction "1_1") (pintype "passive"))
    )
    (net (code "27") (name "/PCIE_UIMC4_SEL") (class "Default")
      (node (ref "IC45") (pin "6") (pinfunction "SEL_6") (pintype "passive"))
    )
    (net (code "28") (name "/PTP_SYNC_SEL") (class "Default")
      (node (ref "IC47") (pin "10") (pinfunction "SEL_10") (pintype "input"))
      (node (ref "R254") (pin "1") (pinfunction "1_1") (pintype "passive"))
    )
    (net (code "29") (name "/RPI_PIN16") (class "Default")
      (node (ref "IC47") (pin "2") (pinfunction "D-_2") (pintype "passive"))
      (node (ref "R245") (pin "2") (pinfunction "2_2") (pintype "passive"))
      (node (ref "R251") (pin "1") (pinfunction "1_1") (pintype "passive"))
    )
    (net (code "30") (name "/RPI_PIN18") (class "Default")
      (node (ref "IC47") (pin "1") (pinfunction "D+_1") (pintype "passive"))
      (node (ref "R244") (pin "2") (pinfunction "2_2") (pintype "passive"))
      (node (ref "R250") (pin "1") (pinfunction "1_1") (pintype "passive"))
    )
    (net (code "31") (name "/RPI_SYNC_IN") (class "Default")
      (node (ref "IC41") (pin "4") (pinfunction "A_4") (pintype "passive"))
      (node (ref "IC49") (pin "4") (pinfunction "B_4") (pintype "bidirectional"))
      (node (ref "R222") (pin "1") (pinfunction "1_1") (pintype "passive"))
      (node (ref "R225") (pin "1") (pinfunction "1_1") (pintype "passive"))
      (node (ref "R255") (pin "1") (pinfunction "1_1") (pintype "passive"))
      (node (ref "R257") (pin "1") (pinfunction "1_1") (pintype "passive"))
    )
    (net (code "32") (name "/RPI_SYNC_IN_LS") (class "Default")
      (node (ref "IC47") (pin "4") (pinfunction "HSD1-_4") (pintype "passive"))
      (node (ref "IC47") (pin "7") (pinfunction "HSD2+_7") (pintype "passive"))
      (node (ref "IC49") (pin "3") (pinfunction "A_3") (pintype "bidirectional"))
      (node (ref "R245") (pin "1") (pinfunction "1_1") (pintype "passive"))
      (node (ref "R257") (pin "2") (pinfunction "2_2") (pintype "passive"))
    )
    (net (code "33") (name "/RPI_SYNC_IN_SEL") (class "Default")
      (node (ref "IC41") (pin "6") (pinfunction "SEL_6") (pintype "passive"))
    )
    (net (code "34") (name "/RPI_SYNC_OUT") (class "Default")
      (node (ref "IC42") (pin "3") (pinfunction "B0_3") (pintype "passive"))
      (node (ref "IC46") (pin "4") (pinfunction "B_4") (pintype "bidirectional"))
      (node (ref "R232") (pin "2") (pinfunction "2_2") (pintype "passive"))
      (node (ref "R247") (pin "1") (pinfunction "1_1") (pintype "passive"))
    )
    (net (code "35") (name "/RPI_SYNC_OUT_LS") (class "Default")
      (node (ref "IC46") (pin "3") (pinfunction "A_3") (pintype "bidirectional"))
      (node (ref "IC47") (pin "5") (pinfunction "HSD1+_5") (pintype "passive"))
      (node (ref "R244") (pin "1") (pinfunction "1_1") (pintype "passive"))
      (node (ref "R246") (pin "1") (pinfunction "1_1") (pintype "passive"))
      (node (ref "R247") (pin "2") (pinfunction "2_2") (pintype "passive"))
    )
    (net (code "36") (name "/SYNC_OUT") (class "Default")
      (node (ref "IC42") (pin "4") (pinfunction "A_4") (pintype "passive"))
      (node (ref "IC43") (pin "3") (pinfunction "B0_3") (pintype "passive"))
      (node (ref "R229") (pin "1") (pinfunction "1_1") (pintype "passive"))
      (node (ref "R232") (pin "1") (pinfunction "1_1") (pintype "passive"))
      (node (ref "R233") (pin "2") (pinfunction "2_2") (pintype "passive"))
    )
    (net (code "37") (name "/SYNC_OUT_SEL") (class "Default")
      (node (ref "IC42") (pin "6") (pinfunction "SEL_6") (pintype "passive"))
    )
    (net (code "38") (name "/XO10_VC") (class "Default")
      (node (ref "XO10") (pin "1") (pinfunction "Vcon_1") (pintype "passive"))
      (node (ref "XO6") (pin "1") (pinfunction "NC/VC_1") (pintype "passive"))
      (node (ref "XO7") (pin "1") (pinfunction "VC_1") (pintype "passive"))
      (node (ref "XO8") (pin "1") (pinfunction "Vc_1") (pintype "passive"))
      (node (ref "XO9") (pin "1") (pinfunction "VCO_1") (pintype "input"))
    )
    (net (code "39") (name "GND") (class "Default")
      (node (ref "C164") (pin "1") (pinfunction "1_1") (pintype "passive"))
      (node (ref "C165") (pin "1") (pinfunction "1_1") (pintype "passive"))
      (node (ref "C166") (pin "2") (pinfunction "2_2") (pintype "passive"))
      (node (ref "C169") (pin "1") (pinfunction "1_1") (pintype "passive"))
      (node (ref "C170") (pin "1") (pinfunction "1_1") (pintype "passive"))
      (node (ref "C171") (pin "1") (pinfunction "1_1") (pintype "passive"))
      (node (ref "C172") (pin "1") (pinfunction "1_1") (pintype "passive"))
      (node (ref "C173") (pin "1") (pinfunction "1_1") (pintype "passive"))
      (node (ref "C174") (pin "1") (pinfunction "1_1") (pintype "passive"))
      (node (ref "C175") (pin "1") (pinfunction "1_1") (pintype "passive"))
      (node (ref "C176") (pin "1") (pinfunction "1_1") (pintype "passive"))
      (node (ref "C177") (pin "1") (pinfunction "1_1") (pintype "passive"))
      (node (ref "C178") (pin "1") (pinfunction "1_1") (pintype "passive"))
      (node (ref "C179") (pin "1") (pinfunction "1_1") (pintype "passive"))
      (node (ref "C180") (pin "1") (pinfunction "1_1") (pintype "passive"))
      (node (ref "C181") (pin "1") (pinfunction "1_1") (pintype "passive"))
      (node (ref "C182") (pin "1") (pinfunction "1_1") (pintype "passive"))
      (node (ref "C183") (pin "1") (pinfunction "1_1") (pintype "passive"))
      (node (ref "C184") (pin "1") (pinfunction "1_1") (pintype "passive"))
      (node (ref "C185") (pin "1") (pinfunction "1_1") (pintype "passive"))
      (node (ref "C186") (pin "1") (pinfunction "1_1") (pintype "passive"))
      (node (ref "C187") (pin "1") (pinfunction "1_1") (pintype "passive"))
      (node (ref "C188") (pin "1") (pinfunction "1_1") (pintype "passive"))
      (node (ref "C189") (pin "1") (pinfunction "1_1") (pintype "passive"))
      (node (ref "C190") (pin "1") (pinfunction "1_1") (pintype "passive"))
      (node (ref "C191") (pin "1") (pinfunction "1_1") (pintype "passive"))
      (node (ref "C192") (pin "1") (pinfunction "1_1") (pintype "passive"))
      (node (ref "C193") (pin "1") (pinfunction "1_1") (pintype "passive"))
      (node (ref "C194") (pin "2") (pinfunction "2_2") (pintype "passive"))
      (node (ref "C195") (pin "2") (pinfunction "2_2") (pintype "passive"))
      (node (ref "C196") (pin "1") (pinfunction "1_1") (pintype "passive"))
      (node (ref "C197") (pin "1") (pinfunction "1_1") (pintype "passive"))
      (node (ref "C198") (pin "1") (pinfunction "1_1") (pintype "passive"))
      (node (ref "C200") (pin "2") (pinfunction "2_2") (pintype "passive"))
      (node (ref "C201") (pin "2") (pinfunction "2_2") (pintype "passive"))
      (node (ref "C202") (pin "2") (pinfunction "2_2") (pintype "passive"))
      (node (ref "C203") (pin "2") (pinfunction "2_2") (pintype "passive"))
      (node (ref "C204") (pin "2") (pinfunction "2_2") (pintype "passive"))
      (node (ref "C205") (pin "1") (pinfunction "1_1") (pintype "passive"))
      (node (ref "C206") (pin "2") (pinfunction "2_2") (pintype "passive"))
      (node (ref "ESD35") (pin "2") (pinfunction "2_2") (pintype "passive"))
      (node (ref "IC39") (pin "1") (pinfunction "GND_1") (pintype "passive"))
      (node (ref "IC39") (pin "11") (pinfunction "GND_11") (pintype "passive"))
      (node (ref "IC39") (pin "12") (pinfunction "GND_12") (pintype "passive"))
      (node (ref "IC39") (pin "16") (pinfunction "GND_16") (pintype "passive"))
      (node (ref "IC39") (pin "19") (pinfunction "GND_19") (pintype "passive"))
      (node (ref "IC39") (pin "22") (pinfunction "SEL_22") (pintype "passive"))
      (node (ref "IC39") (pin "25") (pinfunction "GND_25") (pintype "passive"))
      (node (ref "IC39") (pin "7") (pinfunction "GND_7") (pintype "passive"))
      (node (ref "IC40") (pin "2") (pinfunction "GND_2") (pintype "passive"))
      (node (ref "IC41") (pin "2") (pinfunction "GND_2") (pintype "passive"))
      (node (ref "IC42") (pin "2") (pinfunction "GND_2") (pintype "passive"))
      (node (ref "IC43") (pin "2") (pinfunction "GND_2") (pintype "passive"))
      (node (ref "IC44") (pin "2") (pinfunction "GND_2") (pintype "passive"))
      (node (ref "IC45") (pin "2") (pinfunction "GND_2") (pintype "passive"))
      (node (ref "IC46") (pin "2") (pinfunction "GND_2") (pintype "passive"))
      (node (ref "IC47") (pin "3") (pinfunction "GND_3") (pintype "passive"))
      (node (ref "IC47") (pin "8") (pinfunction "~{OE}_8") (pintype "input"))
      (node (ref "IC48") (pin "10") (pinfunction "GND_10") (pintype "passive"))
      (node (ref "IC48") (pin "12") (pinfunction "GND_12") (pintype "passive"))
      (node (ref "IC48") (pin "13") (pinfunction "GND_13") (pintype "passive"))
      (node (ref "IC48") (pin "24") (pinfunction "GND_24") (pintype "passive"))
      (node (ref "IC49") (pin "2") (pinfunction "GND_2") (pintype "passive"))
      (node (ref "IC49") (pin "5") (pinfunction "DIR_5") (pintype "input"))
      (node (ref "J39") (pin "2") (pinfunction "Y_2") (pintype "passive"))
      (node (ref "J40") (pin "1") (pinfunction "1_1") (pintype "passive"))
      (node (ref "J41") (pin "2") (pinfunction "Y_2") (pintype "passive"))
      (node (ref "R220") (pin "1") (pinfunction "1_1") (pintype "passive"))
      (node (ref "R246") (pin "2") (pinfunction "2_2") (pintype "passive"))
      (node (ref "R250") (pin "2") (pinfunction "2_2") (pintype "passive"))
      (node (ref "R251") (pin "2") (pinfunction "2_2") (pintype "passive"))
      (node (ref "R253") (pin "1") (pinfunction "1_1") (pintype "passive"))
      (node (ref "R254") (pin "2") (pinfunction "2_2") (pintype "passive"))
      (node (ref "R255") (pin "2") (pinfunction "2_2") (pintype "passive"))
      (node (ref "R256") (pin "1") (pinfunction "1_1") (pintype "passive"))
      (node (ref "R259") (pin "1") (pinfunction "1_1") (pintype "passive"))
      (node (ref "XO10") (pin "2") (pinfunction "GND_2") (pintype "passive"))
      (node (ref "XO6") (pin "2") (pinfunction "GND_2") (pintype "passive"))
      (node (ref "XO7") (pin "2") (pinfunction "GND_2") (pintype "passive"))
      (node (ref "XO8") (pin "2") (pinfunction "GND_2") (pintype "passive"))
      (node (ref "XO9") (pin "4") (pinfunction "GND_4") (pintype "passive"))
    )
    (net (code "40") (name "Net-(C167-Pad2)") (class "Default")
      (node (ref "C167") (pin "2") (pinfunction "2_2") (pintype "passive"))
      (node (ref "C168") (pin "1") (pinfunction "1_1") (pintype "passive"))
      (node (ref "R220") (pin "2") (pinfunction "2_2") (pintype "passive"))
    )
    (net (code "41") (name "Net-(C168-Pad2)") (class "Default")
      (node (ref "C168") (pin "2") (pinfunction "2_2") (pintype "passive"))
      (node (ref "R217") (pin "1") (pinfunction "1_1") (pintype "passive"))
      (node (ref "R226") (pin "1") (pinfunction "1_1") (pintype "passive"))
      (node (ref "R234") (pin "2") (pinfunction "2_2") (pintype "passive"))
      (node (ref "R237") (pin "1") (pinfunction "1_1") (pintype "passive"))
    )
    (net (code "42") (name "Net-(C196-Pad2)") (class "Default")
      (node (ref "C196") (pin "2") (pinfunction "2_2") (pintype "passive"))
      (node (ref "L1") (pin "2") (pinfunction "2_2") (pintype "passive"))
      (node (ref "R243") (pin "1") (pinfunction "1_1") (pintype "passive"))
    )
    (net (code "43") (name "Net-(FR9-Pad2)") (class "Default")
      (node (ref "FR9") (pin "2") (pinfunction "2_2") (pintype "passive"))
      (node (ref "R218") (pin "1") (pinfunction "1_1") (pintype "passive"))
      (node (ref "R227") (pin "2") (pinfunction "2_2") (pintype "passive"))
      (node (ref "R231") (pin "1") (pinfunction "1_1") (pintype "passive"))
      (node (ref "R236") (pin "1") (pinfunction "1_1") (pintype "passive"))
    )
    (net (code "44") (name "Net-(IC39-CLKin)") (class "Default")
      (node (ref "C167") (pin "1") (pinfunction "1_1") (pintype "passive"))
      (node (ref "IC39") (pin "21") (pinfunction "CLKin_21") (pintype "passive"))
    )
    (net (code "45") (name "Net-(IC39-CLKin*)") (class "Default")
      (node (ref "C169") (pin "2") (pinfunction "2_2") (pintype "passive"))
      (node (ref "IC39") (pin "20") (pinfunction "CLKin*_20") (pintype "passive"))
    )
    (net (code "46") (name "Net-(IC39-OE)") (class "Default")
      (node (ref "IC39") (pin "24") (pinfunction "OE_24") (pintype "passive"))
      (node (ref "R219") (pin "1") (pinfunction "1_1") (pintype "passive"))
    )
    (net (code "47") (name "Net-(IC44-EN)") (class "Default")
      (node (ref "C189") (pin "2") (pinfunction "2_2") (pintype "passive"))
      (node (ref "C191") (pin "2") (pinfunction "2_2") (pintype "passive"))
      (node (ref "IC44") (pin "1") (pinfunction "IN_1") (pintype "input"))
      (node (ref "IC44") (pin "3") (pinfunction "EN_3") (pintype "input"))
      (node (ref "R236") (pin "2") (pinfunction "2_2") (pintype "passive"))
      (node (ref "R238") (pin "2") (pinfunction "2_2") (pintype "passive"))
    )
    (net (code "48") (name "Net-(IC44-OUT)") (class "Default")
      (node (ref "C190") (pin "2") (pinfunction "2_2") (pintype "passive"))
      (node (ref "C192") (pin "2") (pinfunction "2_2") (pintype "passive"))
      (node (ref "IC44") (pin "5") (pinfunction "OUT_5") (pintype "output"))
      (node (ref "R238") (pin "1") (pinfunction "1_1") (pintype "passive"))
      (node (ref "XO10") (pin "4") (pinfunction "VCC_4") (pintype "passive"))
    )
    (net (code "49") (name "Net-(IC48-D_SEL)") (class "Default")
      (node (ref "IC48") (pin "2") (pinfunction "D_SEL_2") (pintype "passive"))
      (node (ref "R256") (pin "2") (pinfunction "2_2") (pintype "passive"))
    )
    (net (code "50") (name "Net-(IC48-RESET_N)") (class "Default")
      (node (ref "IC48") (pin "8") (pinfunction "RESET_N_8") (pintype "passive"))
      (node (ref "R252") (pin "2") (pinfunction "2_2") (pintype "passive"))
    )
    (net (code "51") (name "Net-(IC48-RF_IN)") (class "Default")
      (node (ref "C199") (pin "2") (pinfunction "2_2") (pintype "passive"))
      (node (ref "IC48") (pin "11") (pinfunction "RF_IN_11") (pintype "passive"))
    )
    (net (code "52") (name "Net-(IC48-SAFEBOOT_N)") (class "Default")
      (node (ref "IC48") (pin "1") (pinfunction "SAFEBOOT_N_1") (pintype "passive"))
      (node (ref "R259") (pin "2") (pinfunction "2_2") (pintype "passive"))
    )
    (net (code "53") (name "Net-(IC48-V_BCKP)") (class "Default")
      (node (ref "C204") (pin "1") (pinfunction "1_1") (pintype "passive"))
      (node (ref "IC48") (pin "22") (pinfunction "V_BCKP_22") (pintype "passive"))
      (node (ref "R258") (pin "1") (pinfunction "1_1") (pintype "passive"))
      (node (ref "R260") (pin "1") (pinfunction "1_1") (pintype "passive"))
    )
    (net (code "54") (name "Net-(J39-X)") (class "Default")
      (node (ref "J39") (pin "1") (pinfunction "X_1") (pintype "passive"))
      (node (ref "R228") (pin "1") (pinfunction "1_1") (pintype "passive"))
    )
    (net (code "55") (name "Net-(J41-X)") (class "Default")
      (node (ref "ESD35") (pin "1") (pinfunction "1_1") (pintype "passive"))
      (node (ref "J41") (pin "1") (pinfunction "X_1") (pintype "passive"))
      (node (ref "R248") (pin "1") (pinfunction "1_1") (pintype "passive"))
    )
    (net (code "56") (name "Net-(R231-Pad2)") (class "Default")
      (node (ref "R231") (pin "2") (pinfunction "2_2") (pintype "passive"))
      (node (ref "R235") (pin "1") (pinfunction "1_1") (pintype "passive"))
    )
    (net (code "57") (name "Net-(R241-Pad1)") (class "Default")
      (node (ref "R241") (pin "1") (pinfunction "1_1") (pintype "passive"))
      (node (ref "R242") (pin "2") (pinfunction "2_2") (pintype "passive"))
      (node (ref "R243") (pin "2") (pinfunction "2_2") (pintype "passive"))
    )
    (net (code "58") (name "Net-(XO6-Output)") (class "Default")
      (node (ref "R217") (pin "2") (pinfunction "2_2") (pintype "passive"))
      (node (ref "XO6") (pin "3") (pinfunction "Output_3") (pintype "output"))
    )
    (net (code "59") (name "Net-(XO6-Vcc)") (class "Default")
      (node (ref "C164") (pin "2") (pinfunction "2_2") (pintype "passive"))
      (node (ref "C165") (pin "2") (pinfunction "2_2") (pintype "passive"))
      (node (ref "C166") (pin "1") (pinfunction "1_1") (pintype "passive"))
      (node (ref "R218") (pin "2") (pinfunction "2_2") (pintype "passive"))
      (node (ref "XO6") (pin "4") (pinfunction "Vcc_4") (pintype "power_in"))
    )
    (net (code "60") (name "Net-(XO7-OUT)") (class "Default")
      (node (ref "R226") (pin "2") (pinfunction "2_2") (pintype "passive"))
      (node (ref "XO7") (pin "4") (pinfunction "OUT_4") (pintype "passive"))
      (node (ref "XO8") (pin "3") (pinfunction "OUT_3") (pintype "passive"))
    )
    (net (code "61") (name "Net-(XO7-TRI-ST.)") (class "Default")
      (node (ref "R223") (pin "1") (pinfunction "1_1") (pintype "passive"))
      (node (ref "XO7") (pin "6") (pinfunction "TRI-ST._6") (pintype "passive"))
    )
    (net (code "62") (name "Net-(XO7-VDD)") (class "Default")
      (node (ref "C172") (pin "2") (pinfunction "2_2") (pintype "passive"))
      (node (ref "C173") (pin "2") (pinfunction "2_2") (pintype "passive"))
      (node (ref "R223") (pin "2") (pinfunction "2_2") (pintype "passive"))
      (node (ref "R227") (pin "1") (pinfunction "1_1") (pintype "passive"))
      (node (ref "XO7") (pin "5") (pinfunction "VDD_5") (pintype "passive"))
      (node (ref "XO8") (pin "4") (pinfunction "VDD_4") (pintype "passive"))
    )
    (net (code "63") (name "Net-(XO9-RF_OUT)") (class "Default")
      (node (ref "R234") (pin "1") (pinfunction "1_1") (pintype "passive"))
      (node (ref "XO9") (pin "6") (pinfunction "RF_OUT_6") (pintype "output"))
    )
    (net (code "64") (name "Net-(XO9-VCC)") (class "Default")
      (node (ref "C178") (pin "2") (pinfunction "2_2") (pintype "passive"))
      (node (ref "C179") (pin "2") (pinfunction "2_2") (pintype "passive"))
      (node (ref "R235") (pin "2") (pinfunction "2_2") (pintype "passive"))
      (node (ref "XO9") (pin "9") (pinfunction "VCC_9") (pintype "power_in"))
    )
    (net (code "65") (name "Net-(XO9-VC_FILTER)") (class "Default")
      (node (ref "C180") (pin "2") (pinfunction "2_2") (pintype "passive"))
      (node (ref "XO9") (pin "7") (pinfunction "VC_FILTER_7") (pintype "input"))
    )
    (net (code "66") (name "Net-(XO10-OUT)") (class "Default")
      (node (ref "R237") (pin "2") (pinfunction "2_2") (pintype "passive"))
      (node (ref "XO10") (pin "3") (pinfunction "OUT_3") (pintype "passive"))
    )
    (net (code "67") (name "VCC3P0_BATT") (class "Default")
      (node (ref "J40") (pin "2") (pinfunction "2_2") (pintype "passive"))
      (node (ref "R258") (pin "2") (pinfunction "2_2") (pintype "passive"))
    )
    (net (code "68") (name "VCC3P3") (class "Default")
      (node (ref "C194") (pin "1") (pinfunction "1_1") (pintype "passive"))
      (node (ref "C195") (pin "1") (pinfunction "1_1") (pintype "passive"))
      (node (ref "C200") (pin "1") (pinfunction "1_1") (pintype "passive"))
      (node (ref "C201") (pin "1") (pinfunction "1_1") (pintype "passive"))
      (node (ref "C203") (pin "1") (pinfunction "1_1") (pintype "passive"))
      (node (ref "IC46") (pin "1") (pinfunction "VCCA_1") (pintype "power_in"))
      (node (ref "IC46") (pin "5") (pinfunction "DIR_5") (pintype "input"))
      (node (ref "IC46") (pin "6") (pinfunction "VCCB_6") (pintype "power_in"))
      (node (ref "IC47") (pin "9") (pinfunction "VCC_9") (pintype "power_in"))
      (node (ref "IC49") (pin "1") (pinfunction "VCCA_1") (pintype "power_in"))
      (node (ref "IC49") (pin "6") (pinfunction "VCCB_6") (pintype "power_in"))
      (node (ref "R249") (pin "1") (pinfunction "1_1") (pintype "passive"))
    )
    (net (code "69") (name "VCC3P3_CLK") (class "Default")
      (node (ref "C170") (pin "2") (pinfunction "2_2") (pintype "passive"))
      (node (ref "C171") (pin "2") (pinfunction "2_2") (pintype "passive"))
      (node (ref "C181") (pin "2") (pinfunction "2_2") (pintype "passive"))
      (node (ref "C182") (pin "2") (pinfunction "2_2") (pintype "passive"))
      (node (ref "C193") (pin "2") (pinfunction "2_2") (pintype "passive"))
      (node (ref "IC40") (pin "5") (pinfunction "VCC_5") (pintype "passive"))
      (node (ref "IC41") (pin "5") (pinfunction "VCC_5") (pintype "passive"))
      (node (ref "IC42") (pin "5") (pinfunction "VCC_5") (pintype "passive"))
      (node (ref "IC43") (pin "5") (pinfunction "VCC_5") (pintype "passive"))
      (node (ref "IC45") (pin "5") (pinfunction "VCC_5") (pintype "passive"))
    )
    (net (code "70") (name "VCC3P3_CLK2") (class "Default")
      (node (ref "FR10") (pin "1") (pinfunction "1_1") (pintype "passive"))
      (node (ref "FR11") (pin "1") (pinfunction "1_1") (pintype "passive"))
      (node (ref "FR12") (pin "1") (pinfunction "1_1") (pintype "passive"))
      (node (ref "FR9") (pin "1") (pinfunction "1_1") (pintype "passive"))
    )
    (net (code "71") (name "VCC3P3_GNSS") (class "Default")
      (node (ref "C197") (pin "2") (pinfunction "2_2") (pintype "passive"))
      (node (ref "C198") (pin "2") (pinfunction "2_2") (pintype "passive"))
      (node (ref "C205") (pin "2") (pinfunction "2_2") (pintype "passive"))
      (node (ref "C206") (pin "1") (pinfunction "1_1") (pintype "passive"))
      (node (ref "FR12") (pin "2") (pinfunction "2_2") (pintype "passive"))
      (node (ref "IC48") (pin "23") (pinfunction "VCC_23") (pintype "passive"))
      (node (ref "R242") (pin "1") (pinfunction "1_1") (pintype "passive"))
      (node (ref "R260") (pin "2") (pinfunction "2_2") (pintype "passive"))
    )
    (net (code "72") (name "VCC3P3_LMK10") (class "Default")
      (node (ref "C174") (pin "2") (pinfunction "2_2") (pintype "passive"))
      (node (ref "C175") (pin "2") (pinfunction "2_2") (pintype "passive"))
      (node (ref "C176") (pin "2") (pinfunction "2_2") (pintype "passive"))
      (node (ref "C177") (pin "2") (pinfunction "2_2") (pintype "passive"))
      (node (ref "FR10") (pin "2") (pinfunction "2_2") (pintype "passive"))
      (node (ref "IC39") (pin "23") (pinfunction "Vdd_23") (pintype "passive"))
      (node (ref "IC39") (pin "8") (pinfunction "Vdd_8") (pintype "passive"))
      (node (ref "R219") (pin "2") (pinfunction "2_2") (pintype "passive"))
    )
    (net (code "73") (name "VCC3P3_LMK10_VDDO") (class "Default")
      (node (ref "C183") (pin "2") (pinfunction "2_2") (pintype "passive"))
      (node (ref "C184") (pin "2") (pinfunction "2_2") (pintype "passive"))
      (node (ref "C185") (pin "2") (pinfunction "2_2") (pintype "passive"))
      (node (ref "C186") (pin "2") (pinfunction "2_2") (pintype "passive"))
      (node (ref "C187") (pin "2") (pinfunction "2_2") (pintype "passive"))
      (node (ref "C188") (pin "2") (pinfunction "2_2") (pintype "passive"))
      (node (ref "FR11") (pin "2") (pinfunction "2_2") (pintype "passive"))
      (node (ref "IC39") (pin "14") (pinfunction "Vddo_14") (pintype "passive"))
      (node (ref "IC39") (pin "18") (pinfunction "Vddo_18") (pintype "passive"))
      (node (ref "IC39") (pin "2") (pinfunction "Vddo_2") (pintype "passive"))
      (node (ref "IC39") (pin "6") (pinfunction "Vddo_6") (pintype "passive"))
    )
    (net (code "74") (name "unconnected-(IC39-CLKout1-Pad5)") (class "Default")
      (node (ref "IC39") (pin "5") (pinfunction "CLKout1_5") (pintype "passive+no_connect"))
    )
    (net (code "75") (name "unconnected-(IC39-OSCin-Pad9)") (class "Default")
      (node (ref "IC39") (pin "9") (pinfunction "OSCin_9") (pintype "passive+no_connect"))
    )
    (net (code "76") (name "unconnected-(IC39-OSCout-Pad10)") (class "Default")
      (node (ref "IC39") (pin "10") (pinfunction "OSCout_10") (pintype "passive+no_connect"))
    )
    (net (code "77") (name "unconnected-(IC44-NC-Pad4)") (class "Default")
      (node (ref "IC44") (pin "4") (pinfunction "NC_4") (pintype "passive+no_connect"))
    )
    (net (code "78") (name "unconnected-(IC47-HSD2--Pad6)") (class "Default")
      (node (ref "IC47") (pin "6") (pinfunction "HSD2-_6") (pintype "passive+no_connect"))
    )
    (net (code "79") (name "unconnected-(IC48-GEOFENCE_STAT{slash}RESV-Pad16)") (class "Default")
      (node (ref "IC48") (pin "16") (pinfunction "GEOFENCE_STAT/RESV_16") (pintype "passive+no_connect"))
    )
    (net (code "80") (name "unconnected-(IC48-LNA_EN{slash}RESV-Pad14)") (class "Default")
      (node (ref "IC48") (pin "14") (pinfunction "LNA_EN/RESV_14") (pintype "passive+no_connect"))
    )
    (net (code "81") (name "unconnected-(IC48-RESV-Pad17)") (class "Default")
      (node (ref "IC48") (pin "17") (pinfunction "RESV_17") (pintype "passive+no_connect"))
    )
    (net (code "82") (name "unconnected-(IC48-RTK_STAT{slash}RESV-Pad15)") (class "Default")
      (node (ref "IC48") (pin "15") (pinfunction "RTK_STAT/RESV_15") (pintype "passive+no_connect"))
    )
    (net (code "83") (name "unconnected-(XO7-T.S.-Pad3)") (class "Default")
      (node (ref "XO7") (pin "3") (pinfunction "T.S._3") (pintype "passive+no_connect"))
    )
    (net (code "84") (name "unconnected-(XO9-NC-Pad2)") (class "Default")
      (node (ref "XO9") (pin "2") (pinfunction "NC_2") (pintype "passive+no_connect"))
    )
    (net (code "85") (name "unconnected-(XO9-NC-Pad3)") (class "Default")
      (node (ref "XO9") (pin "3") (pinfunction "NC_3") (pintype "passive+no_connect"))
    )
    (net (code "86") (name "unconnected-(XO9-NC-Pad5)") (class "Default")
      (node (ref "XO9") (pin "5") (pinfunction "NC_5") (pintype "passive+no_connect"))
    )
    (net (code "87") (name "unconnected-(XO9-NC-Pad8)") (class "Default")
      (node (ref "XO9") (pin "8") (pinfunction "NC_8") (pintype "passive+no_connect"))
    )
    (net (code "88") (name "unconnected-(XO9-NC-Pad10)") (class "Default")
      (node (ref "XO9") (pin "10") (pinfunction "NC_10") (pintype "passive+no_connect"))
    )
  )
)
